# Doorbell.net
KiCad netlist of a schematic drawn in EAGLE
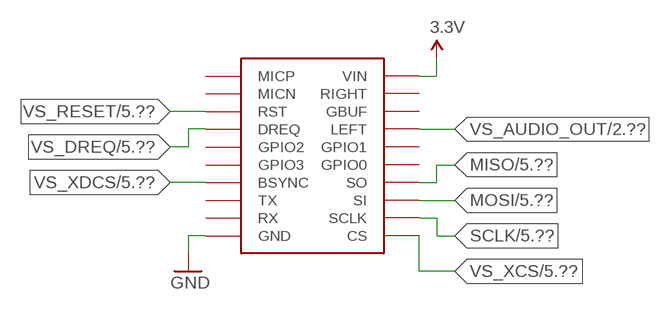
[diagram p0: schematic, sheet 1]
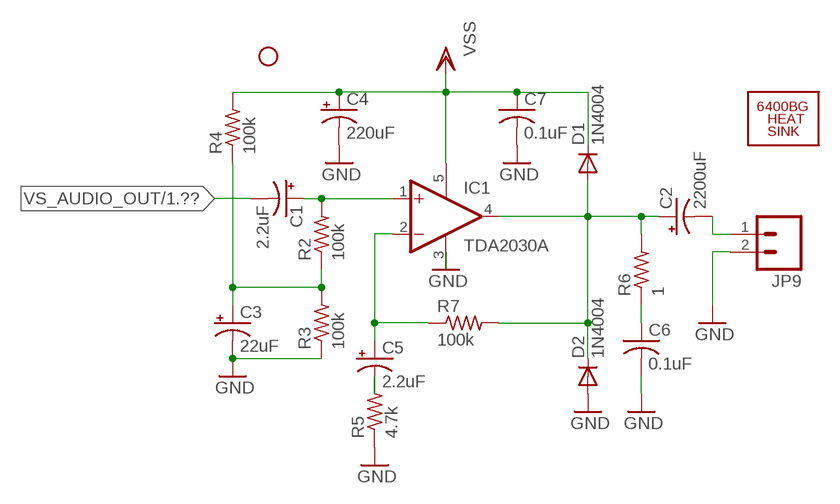
[diagram p1: schematic, sheet 2]
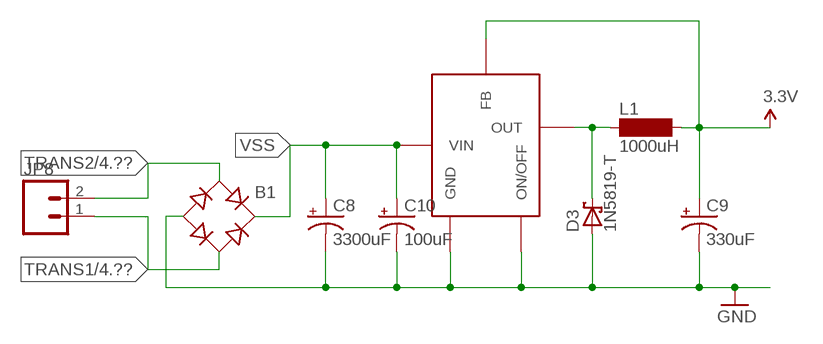
[diagram p2: schematic, sheet 3]
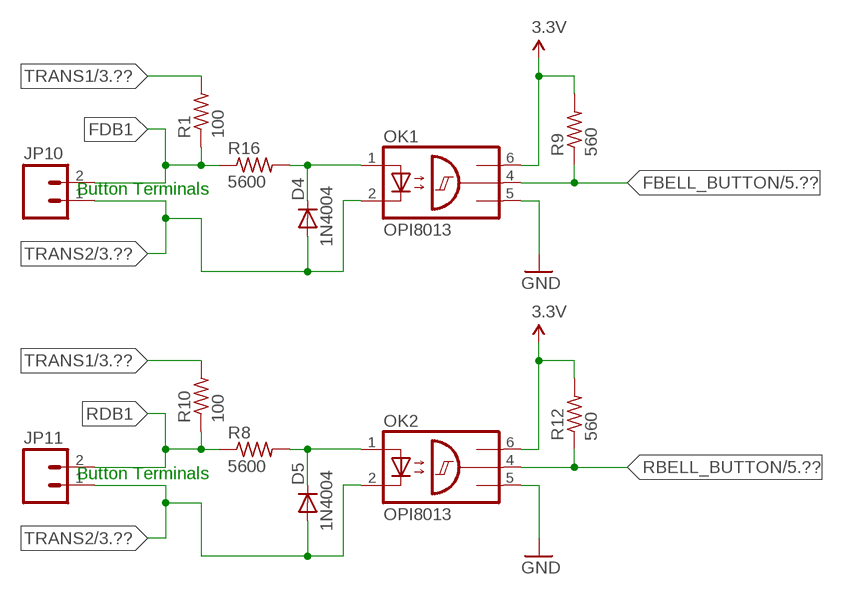
[diagram p3: schematic, sheet 4]
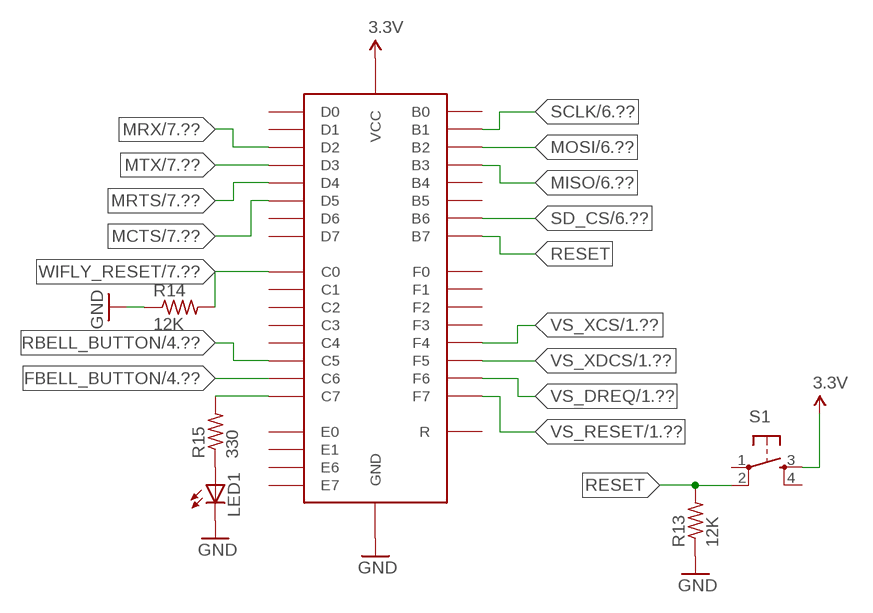
[diagram p4: schematic, sheet 5]
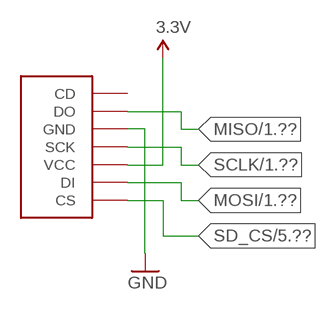
[diagram p5: schematic, sheet 6]
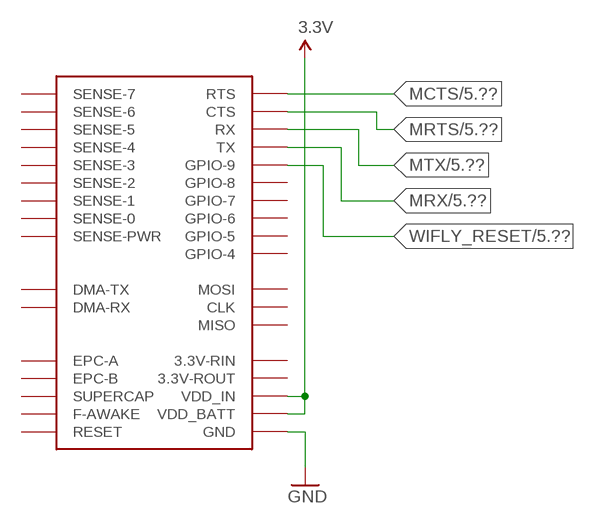
[diagram p6: schematic, sheet 7]

(export (version "E")
  (design (tool "Eeschema 10.0.6"))
  (components
    (comp (ref "U$6")
      (value "WIFLY_BREAKOUT")
      (footprint "eagle-import:SPARKFUN_1X17")
      (libsource (lib "eagle-import") (part "WIFLY_BREAKOUT"))
    )
    (comp (ref "C1")
      (value "2.2uF")
      (footprint "eagle-import:E2-5")
      (libsource (lib "eagle-import") (part "CPOL-USE2-5"))
    )
    (comp (ref "C2")
      (value "2200uF")
      (footprint "eagle-import:E7,5-16")
      (libsource (lib "eagle-import") (part "CPOL-USE7.5-16"))
    )
    (comp (ref "C3")
      (value "22uF")
      (footprint "eagle-import:E2-5")
      (libsource (lib "eagle-import") (part "CPOL-USE2-5"))
    )
    (comp (ref "C4")
      (value "220uF")
      (footprint "eagle-import:E5-10,5")
      (libsource (lib "eagle-import") (part "CPOL-USE5-10.5"))
    )
    (comp (ref "C5")
      (value "2.2uF")
      (footprint "eagle-import:E2-5")
      (libsource (lib "eagle-import") (part "CPOL-USE2-5"))
    )
    (comp (ref "C6")
      (value "0.1uF")
      (footprint "eagle-import:C025-030X050")
      (libsource (lib "eagle-import") (part "C-US025-030X050"))
    )
    (comp (ref "C7")
      (value "0.1uF")
      (footprint "eagle-import:C025-030X050")
      (libsource (lib "eagle-import") (part "C-US025-030X050"))
    )
    (comp (ref "D1")
      (value "1N4004")
      (footprint "eagle-import:DO41-10")
      (libsource (lib "eagle-import") (part "1N4004"))
    )
    (comp (ref "D2")
      (value "1N4004")
      (footprint "eagle-import:DO41-10")
      (libsource (lib "eagle-import") (part "1N4004"))
    )
    (comp (ref "IC1")
      (value "TDA2030A")
      (footprint "eagle-import:CB360")
      (libsource (lib "eagle-import") (part "TDA2030V"))
    )
    (comp (ref "JP7")
      (value "STAND-OFF")
      (footprint "eagle-import:STAND-OFF")
      (libsource (lib "eagle-import") (part "STAND-OFF"))
    )
    (comp (ref "JP9")
      (value "M025MM")
      (footprint "eagle-import:SCREWTERMINAL-5MM-2")
      (libsource (lib "eagle-import") (part "M025MM"))
    )
    (comp (ref "R2")
      (value "100k")
      (footprint "eagle-import:0207_7")
      (libsource (lib "eagle-import") (part "R-US_0207/7"))
    )
    (comp (ref "R3")
      (value "100k")
      (footprint "eagle-import:0207_7")
      (libsource (lib "eagle-import") (part "R-US_0207/7"))
    )
    (comp (ref "R4")
      (value "100k")
      (footprint "eagle-import:0207_7")
      (libsource (lib "eagle-import") (part "R-US_0207/7"))
    )
    (comp (ref "R5")
      (value "4.7k")
      (footprint "eagle-import:0207_7")
      (libsource (lib "eagle-import") (part "R-US_0207/7"))
    )
    (comp (ref "R6")
      (value "1")
      (footprint "eagle-import:0207_7")
      (libsource (lib "eagle-import") (part "R-US_0207/7"))
    )
    (comp (ref "R7")
      (value "100k")
      (footprint "eagle-import:0207_7")
      (libsource (lib "eagle-import") (part "R-US_0207/7"))
    )
    (comp (ref "U$1")
      (value "6400BG_HEATSINK")
      (footprint "eagle-import:6400BG_HEATSINK")
      (libsource (lib "eagle-import") (part "6400BG_HEATSINK"))
    )
    (comp (ref "LED1")
      (value "LED3MM")
      (footprint "eagle-import:LED3MM")
      (libsource (lib "eagle-import") (part "LED3MM"))
    )
    (comp (ref "R13")
      (value "12K")
      (footprint "eagle-import:0207_7")
      (libsource (lib "eagle-import") (part "resistor_R-US_0207/7"))
    )
    (comp (ref "R14")
      (value "12K")
      (footprint "eagle-import:0207_7")
      (libsource (lib "eagle-import") (part "resistor_R-US_0207/7"))
    )
    (comp (ref "R15")
      (value "330")
      (footprint "eagle-import:0207_7")
      (libsource (lib "eagle-import") (part "resistor_R-US_0207/7"))
    )
    (comp (ref "S1")
      (value "TAC_SWITCHPTH")
      (footprint "eagle-import:TACTILE-PTH")
      (libsource (lib "eagle-import") (part "TAC_SWITCHPTH"))
    )
    (comp (ref "U$4")
      (value "AT90USB1286AT90USB1286BREAKOUT")
      (footprint "eagle-import:ADAFRUIT_1X10-BIG")
      (libsource (lib "eagle-import") (part "AT90USB1286AT90USB1286BREAKOUT"))
    )
    (comp (ref "U$3")
      (value "VS1011E")
      (footprint "eagle-import:ADAFRUIT_1X10-BIG")
      (libsource (lib "eagle-import") (part "VS1011E"))
    )
    (comp (ref "B1")
      (value "DBDB101G")
      (footprint "eagle-import:DB")
      (libsource (lib "eagle-import") (part "DB?GDB101"))
    )
    (comp (ref "C8")
      (value "3300uF")
      (footprint "eagle-import:E7,5-18")
      (libsource (lib "eagle-import") (part "CPOL-USE7.5-18"))
    )
    (comp (ref "C9")
      (value "330uF")
      (footprint "eagle-import:E5-8,5")
      (libsource (lib "eagle-import") (part "CPOL-USE5-8.5"))
    )
    (comp (ref "C10")
      (value "100uF")
      (footprint "eagle-import:E5-8,5")
      (libsource (lib "eagle-import") (part "CPOL-USE5-8.5"))
    )
    (comp (ref "D3")
      (value "1N5819-T")
      (footprint "eagle-import:DO41-7.6")
      (libsource (lib "eagle-import") (part "1N5819-T"))
    )
    (comp (ref "JP8")
      (value "M025MM")
      (footprint "eagle-import:SCREWTERMINAL-5MM-2")
      (libsource (lib "eagle-import") (part "M025MM"))
    )
    (comp (ref "L1")
      (value "1000uH")
      (footprint "eagle-import:BS11")
      (libsource (lib "eagle-import") (part "BS11"))
    )
    (comp (ref "U$2")
      (value "LM2575")
      (footprint "eagle-import:LINEAR-TECHNOLOGY_TO220-5")
      (libsource (lib "eagle-import") (part "LM2575"))
    )
    (comp (ref "D4")
      (value "1N4004")
      (footprint "eagle-import:DO41-10")
      (libsource (lib "eagle-import") (part "1N4004"))
    )
    (comp (ref "D5")
      (value "1N4004")
      (footprint "eagle-import:DO41-10")
      (libsource (lib "eagle-import") (part "1N4004"))
    )
    (comp (ref "JP10")
      (value "M025MM")
      (footprint "eagle-import:SCREWTERMINAL-5MM-2")
      (libsource (lib "eagle-import") (part "M025MM"))
    )
    (comp (ref "JP11")
      (value "M025MM")
      (footprint "eagle-import:SCREWTERMINAL-5MM-2")
      (libsource (lib "eagle-import") (part "M025MM"))
    )
    (comp (ref "OK1")
      (value "OPI8013")
      (footprint "eagle-import:DIL06")
      (libsource (lib "eagle-import") (part "OPI8013"))
    )
    (comp (ref "OK2")
      (value "OPI8013")
      (footprint "eagle-import:DIL06")
      (libsource (lib "eagle-import") (part "OPI8013"))
    )
    (comp (ref "R1")
      (value "100")
      (footprint "eagle-import:P0817_22")
      (libsource (lib "eagle-import") (part "R-US_0817/22"))
    )
    (comp (ref "R8")
      (value "5600")
      (footprint "eagle-import:0207_12")
      (libsource (lib "eagle-import") (part "resistor_R-US_0207/12"))
    )
    (comp (ref "R9")
      (value "560")
      (footprint "eagle-import:0207_7")
      (libsource (lib "eagle-import") (part "R-US_0207/7"))
    )
    (comp (ref "R10")
      (value "100")
      (footprint "eagle-import:P0817_22")
      (libsource (lib "eagle-import") (part "R-US_0817/22"))
    )
    (comp (ref "R12")
      (value "560")
      (footprint "eagle-import:0207_7")
      (libsource (lib "eagle-import") (part "R-US_0207/7"))
    )
    (comp (ref "R16")
      (value "5600")
      (footprint "eagle-import:0207_12")
      (libsource (lib "eagle-import") (part "resistor_R-US_0207/12"))
    )
    (comp (ref "U$5")
      (value "MICROSDMICROSDBREAKOUT")
      (footprint "eagle-import:ADAFRUIT_1X08-BIG")
      (libsource (lib "eagle-import") (part "MICROSDMICROSDBREAKOUT"))
    )
  )
  (nets
    (net (code "1") (name "3.3V") (class "Default")
      (node (ref "C9") (pin "+") (pinfunction "+_+") (pintype "passive"))
      (node (ref "L1") (pin "2") (pinfunction "2_2") (pintype "passive"))
      (node (ref "OK1") (pin "6") (pinfunction "VCC_6") (pintype "passive"))
      (node (ref "OK2") (pin "6") (pinfunction "VCC_6") (pintype "passive"))
      (node (ref "R12") (pin "2") (pinfunction "2_2") (pintype "passive"))
      (node (ref "R9") (pin "2") (pinfunction "2_2") (pintype "passive"))
      (node (ref "S1") (pin "3") (pinfunction "3_3") (pintype "passive"))
      (node (ref "U$2") (pin "FB") (pinfunction "FB_FB") (pintype "input"))
      (node (ref "U$3") (pin "VIN") (pinfunction "VIN_VIN") (pintype "bidirectional"))
      (node (ref "U$4") (pin "VCC") (pinfunction "VCC_VCC") (pintype "bidirectional"))
      (node (ref "U$5") (pin "VCC") (pinfunction "VCC_VCC") (pintype "bidirectional"))
      (node (ref "U$6") (pin "VDD_BATT") (pinfunction "VDD_BATT_VDD_BATT") (pintype "bidirectional"))
      (node (ref "U$6") (pin "VDD_IN") (pinfunction "VDD_IN_VDD_IN") (pintype "bidirectional"))
    )
    (net (code "2") (name "FBELL_BUTTON") (class "Default")
      (node (ref "OK1") (pin "4") (pinfunction "OUT_4") (pintype "passive"))
      (node (ref "R9") (pin "1") (pinfunction "1_1") (pintype "passive"))
      (node (ref "U$4") (pin "C6") (pinfunction "C6_C6") (pintype "bidirectional"))
    )
    (net (code "3") (name "FDB1") (class "Default")
      (node (ref "JP10") (pin "2") (pinfunction "2_2") (pintype "passive"))
      (node (ref "R1") (pin "1") (pinfunction "1_1") (pintype "passive"))
      (node (ref "R16") (pin "1") (pinfunction "1_1") (pintype "passive"))
    )
    (net (code "4") (name "GND") (class "Default")
      (node (ref "B1") (pin "-") (pinfunction "-_-") (pintype "passive"))
      (node (ref "C10") (pin "-") (pinfunction "-_-") (pintype "passive"))
      (node (ref "C3") (pin "-") (pinfunction "-_-") (pintype "passive"))
      (node (ref "C4") (pin "-") (pinfunction "-_-") (pintype "passive"))
      (node (ref "C6") (pin "2") (pinfunction "2_2") (pintype "passive"))
      (node (ref "C7") (pin "2") (pinfunction "2_2") (pintype "passive"))
      (node (ref "C8") (pin "-") (pinfunction "-_-") (pintype "passive"))
      (node (ref "C9") (pin "-") (pinfunction "-_-") (pintype "passive"))
      (node (ref "D2") (pin "A") (pinfunction "A_A") (pintype "passive"))
      (node (ref "D3") (pin "A") (pinfunction "A_A") (pintype "passive"))
      (node (ref "IC1") (pin "3") (pinfunction "GND_3") (pintype "power_in"))
      (node (ref "JP9") (pin "2") (pinfunction "2_2") (pintype "passive"))
      (node (ref "LED1") (pin "K") (pinfunction "C_K") (pintype "passive"))
      (node (ref "OK1") (pin "5") (pinfunction "GND_5") (pintype "passive"))
      (node (ref "OK2") (pin "5") (pinfunction "GND_5") (pintype "passive"))
      (node (ref "R13") (pin "1") (pinfunction "1_1") (pintype "passive"))
      (node (ref "R14") (pin "1") (pinfunction "1_1") (pintype "passive"))
      (node (ref "R3") (pin "1") (pinfunction "1_1") (pintype "passive"))
      (node (ref "R5") (pin "1") (pinfunction "1_1") (pintype "passive"))
      (node (ref "U$2") (pin "GND") (pinfunction "GND_GND") (pintype "power_in"))
      (node (ref "U$2") (pin "ON/OFF") (pinfunction "ON/OFF_ON/OFF") (pintype "input"))
      (node (ref "U$3") (pin "GND") (pinfunction "GND_GND") (pintype "bidirectional"))
      (node (ref "U$4") (pin "GND") (pinfunction "GND_GND") (pintype "bidirectional"))
      (node (ref "U$5") (pin "GND") (pinfunction "GND_GND") (pintype "bidirectional"))
      (node (ref "U$6") (pin "GND") (pinfunction "GND_GND") (pintype "bidirectional"))
    )
    (net (code "5") (name "MCTS") (class "Default")
      (node (ref "U$4") (pin "D5") (pinfunction "D5_D5") (pintype "bidirectional"))
      (node (ref "U$6") (pin "RTS") (pinfunction "RTS_RTS") (pintype "bidirectional"))
    )
    (net (code "6") (name "MISO") (class "Default")
      (node (ref "U$3") (pin "SO") (pinfunction "SO_SO") (pintype "bidirectional"))
      (node (ref "U$4") (pin "B3") (pinfunction "B3_B3") (pintype "bidirectional"))
      (node (ref "U$5") (pin "DO") (pinfunction "DO_DO") (pintype "bidirectional"))
    )
    (net (code "7") (name "MOSI") (class "Default")
      (node (ref "U$3") (pin "SI") (pinfunction "SI_SI") (pintype "bidirectional"))
      (node (ref "U$4") (pin "B2") (pinfunction "B2_B2") (pintype "bidirectional"))
      (node (ref "U$5") (pin "DI") (pinfunction "DI_DI") (pintype "bidirectional"))
    )
    (net (code "8") (name "MRTS") (class "Default")
      (node (ref "U$4") (pin "D4") (pinfunction "D4_D4") (pintype "bidirectional"))
      (node (ref "U$6") (pin "CTS") (pinfunction "CTS_CTS") (pintype "bidirectional"))
    )
    (net (code "9") (name "MRX") (class "Default")
      (node (ref "U$4") (pin "D2") (pinfunction "D2_D2") (pintype "bidirectional"))
      (node (ref "U$6") (pin "TX") (pinfunction "TX_TX") (pintype "bidirectional"))
    )
    (net (code "10") (name "MTX") (class "Default")
      (node (ref "U$4") (pin "D3") (pinfunction "D3_D3") (pintype "bidirectional"))
      (node (ref "U$6") (pin "RX") (pinfunction "RX_RX") (pintype "bidirectional"))
    )
    (net (code "11") (name "Net-(C2-Pad-)") (class "Default")
      (node (ref "C2") (pin "-") (pinfunction "-_-") (pintype "passive"))
      (node (ref "JP9") (pin "1") (pinfunction "1_1") (pintype "passive"))
    )
    (net (code "12") (name "Net-(C3-Pad+)") (class "Default")
      (node (ref "C3") (pin "+") (pinfunction "+_+") (pintype "passive"))
      (node (ref "R2") (pin "1") (pinfunction "1_1") (pintype "passive"))
      (node (ref "R3") (pin "2") (pinfunction "2_2") (pintype "passive"))
      (node (ref "R4") (pin "1") (pinfunction "1_1") (pintype "passive"))
    )
    (net (code "13") (name "Net-(C5-Pad-)") (class "Default")
      (node (ref "C5") (pin "-") (pinfunction "-_-") (pintype "passive"))
      (node (ref "R5") (pin "2") (pinfunction "2_2") (pintype "passive"))
    )
    (net (code "14") (name "Net-(C6-Pad1)") (class "Default")
      (node (ref "C6") (pin "1") (pinfunction "1_1") (pintype "passive"))
      (node (ref "R6") (pin "1") (pinfunction "1_1") (pintype "passive"))
    )
    (net (code "15") (name "Net-(D3-PadC)") (class "Default")
      (node (ref "D3") (pin "C") (pinfunction "C_C") (pintype "passive"))
      (node (ref "L1") (pin "1") (pinfunction "1_1") (pintype "passive"))
      (node (ref "U$2") (pin "OUT") (pinfunction "OUT_OUT") (pintype "power_in"))
    )
    (net (code "16") (name "Net-(IC1-+IN)") (class "Default")
      (node (ref "C1") (pin "+") (pinfunction "+_+") (pintype "passive"))
      (node (ref "IC1") (pin "1") (pinfunction "+IN_1") (pintype "input"))
      (node (ref "R2") (pin "2") (pinfunction "2_2") (pintype "passive"))
    )
    (net (code "17") (name "Net-(IC1--IN)") (class "Default")
      (node (ref "C5") (pin "+") (pinfunction "+_+") (pintype "passive"))
      (node (ref "IC1") (pin "2") (pinfunction "-IN_2") (pintype "input"))
      (node (ref "R7") (pin "1") (pinfunction "1_1") (pintype "passive"))
    )
    (net (code "18") (name "Net-(IC1-OUT)") (class "Default")
      (node (ref "C2") (pin "+") (pinfunction "+_+") (pintype "passive"))
      (node (ref "D1") (pin "A") (pinfunction "A_A") (pintype "passive"))
      (node (ref "D2") (pin "C") (pinfunction "C_C") (pintype "passive"))
      (node (ref "IC1") (pin "4") (pinfunction "OUT_4") (pintype "output"))
      (node (ref "R6") (pin "2") (pinfunction "2_2") (pintype "passive"))
      (node (ref "R7") (pin "2") (pinfunction "2_2") (pintype "passive"))
    )
    (net (code "19") (name "Net-(LED1-PadA)") (class "Default")
      (node (ref "LED1") (pin "A") (pinfunction "A_A") (pintype "passive"))
      (node (ref "R15") (pin "1") (pinfunction "1_1") (pintype "passive"))
    )
    (net (code "20") (name "Net-(OK1-A)") (class "Default")
      (node (ref "D4") (pin "C") (pinfunction "C_C") (pintype "passive"))
      (node (ref "OK1") (pin "1") (pinfunction "A_1") (pintype "passive"))
      (node (ref "R16") (pin "2") (pinfunction "2_2") (pintype "passive"))
    )
    (net (code "21") (name "Net-(OK2-A)") (class "Default")
      (node (ref "D5") (pin "C") (pinfunction "C_C") (pintype "passive"))
      (node (ref "OK2") (pin "1") (pinfunction "A_1") (pintype "passive"))
      (node (ref "R8") (pin "2") (pinfunction "2_2") (pintype "passive"))
    )
    (net (code "22") (name "Net-(R15-Pad2)") (class "Default")
      (node (ref "R15") (pin "2") (pinfunction "2_2") (pintype "passive"))
      (node (ref "U$4") (pin "C7") (pinfunction "C7_C7") (pintype "bidirectional"))
    )
    (net (code "23") (name "RBELL_BUTTON") (class "Default")
      (node (ref "OK2") (pin "4") (pinfunction "OUT_4") (pintype "passive"))
      (node (ref "R12") (pin "1") (pinfunction "1_1") (pintype "passive"))
      (node (ref "U$4") (pin "C5") (pinfunction "C5_C5") (pintype "bidirectional"))
    )
    (net (code "24") (name "RDB1") (class "Default")
      (node (ref "JP11") (pin "2") (pinfunction "2_2") (pintype "passive"))
      (node (ref "R10") (pin "1") (pinfunction "1_1") (pintype "passive"))
      (node (ref "R8") (pin "1") (pinfunction "1_1") (pintype "passive"))
    )
    (net (code "25") (name "RESET") (class "Default")
      (node (ref "R13") (pin "2") (pinfunction "2_2") (pintype "passive"))
      (node (ref "S1") (pin "2") (pinfunction "2_2") (pintype "passive"))
      (node (ref "U$4") (pin "B7") (pinfunction "B7_B7") (pintype "bidirectional"))
    )
    (net (code "26") (name "SCLK") (class "Default")
      (node (ref "U$3") (pin "SCLK") (pinfunction "SCLK_SCLK") (pintype "bidirectional"))
      (node (ref "U$4") (pin "B1") (pinfunction "B1_B1") (pintype "bidirectional"))
      (node (ref "U$5") (pin "SCK") (pinfunction "SCK_SCK") (pintype "bidirectional"))
    )
    (net (code "27") (name "SD_CS") (class "Default")
      (node (ref "U$4") (pin "B6") (pinfunction "B6_B6") (pintype "bidirectional"))
      (node (ref "U$5") (pin "CS") (pinfunction "CS_CS") (pintype "bidirectional"))
    )
    (net (code "28") (name "TRANS1") (class "Default")
      (node (ref "B1") (pin "AC2") (pinfunction "AC2_AC2") (pintype "passive"))
      (node (ref "JP8") (pin "1") (pinfunction "1_1") (pintype "passive"))
      (node (ref "R1") (pin "2") (pinfunction "2_2") (pintype "passive"))
      (node (ref "R10") (pin "2") (pinfunction "2_2") (pintype "passive"))
    )
    (net (code "29") (name "TRANS2") (class "Default")
      (node (ref "B1") (pin "AC1") (pinfunction "AC1_AC1") (pintype "passive"))
      (node (ref "D4") (pin "A") (pinfunction "A_A") (pintype "passive"))
      (node (ref "D5") (pin "A") (pinfunction "A_A") (pintype "passive"))
      (node (ref "JP10") (pin "1") (pinfunction "1_1") (pintype "passive"))
      (node (ref "JP11") (pin "1") (pinfunction "1_1") (pintype "passive"))
      (node (ref "JP8") (pin "2") (pinfunction "2_2") (pintype "passive"))
      (node (ref "OK1") (pin "2") (pinfunction "C_2") (pintype "passive"))
      (node (ref "OK2") (pin "2") (pinfunction "C_2") (pintype "passive"))
    )
    (net (code "30") (name "VSS") (class "Default")
      (node (ref "B1") (pin "+") (pinfunction "+_+") (pintype "passive"))
      (node (ref "C10") (pin "+") (pinfunction "+_+") (pintype "passive"))
      (node (ref "C4") (pin "+") (pinfunction "+_+") (pintype "passive"))
      (node (ref "C7") (pin "1") (pinfunction "1_1") (pintype "passive"))
      (node (ref "C8") (pin "+") (pinfunction "+_+") (pintype "passive"))
      (node (ref "D1") (pin "C") (pinfunction "C_C") (pintype "passive"))
      (node (ref "IC1") (pin "5") (pinfunction "V+_5") (pintype "power_in"))
      (node (ref "R4") (pin "2") (pinfunction "2_2") (pintype "passive"))
      (node (ref "U$2") (pin "VIN") (pinfunction "VIN_VIN") (pintype "power_in"))
    )
    (net (code "31") (name "VS_AUDIO_OUT") (class "Default")
      (node (ref "C1") (pin "-") (pinfunction "-_-") (pintype "passive"))
      (node (ref "U$3") (pin "LEFT") (pinfunction "LEFT_LEFT") (pintype "bidirectional"))
    )
    (net (code "32") (name "VS_DREQ") (class "Default")
      (node (ref "U$3") (pin "DREQ") (pinfunction "DREQ_DREQ") (pintype "bidirectional"))
      (node (ref "U$4") (pin "F6") (pinfunction "F6_F6") (pintype "bidirectional"))
    )
    (net (code "33") (name "VS_RESET") (class "Default")
      (node (ref "U$3") (pin "RST") (pinfunction "RST_RST") (pintype "bidirectional"))
      (node (ref "U$4") (pin "F7") (pinfunction "F7_F7") (pintype "bidirectional"))
    )
    (net (code "34") (name "VS_XCS") (class "Default")
      (node (ref "U$3") (pin "CS") (pinfunction "CS_CS") (pintype "bidirectional"))
      (node (ref "U$4") (pin "F4") (pinfunction "F4_F4") (pintype "bidirectional"))
    )
    (net (code "35") (name "VS_XDCS") (class "Default")
      (node (ref "U$3") (pin "BSYNC") (pinfunction "BSYNC_BSYNC") (pintype "bidirectional"))
      (node (ref "U$4") (pin "F5") (pinfunction "F5_F5") (pintype "bidirectional"))
    )
    (net (code "36") (name "WIFLY_RESET") (class "Default")
      (node (ref "R14") (pin "2") (pinfunction "2_2") (pintype "passive"))
      (node (ref "U$4") (pin "C0") (pinfunction "C0_C0") (pintype "bidirectional"))
      (node (ref "U$6") (pin "GPIO-9") (pinfunction "GPIO-9_GPIO-9") (pintype "bidirectional"))
    )
    (net (code "37") (name "unconnected-(S1-Pad1)") (class "Default")
      (node (ref "S1") (pin "1") (pinfunction "1_1") (pintype "passive"))
    )
    (net (code "38") (name "unconnected-(S1-Pad4)") (class "Default")
      (node (ref "S1") (pin "4") (pinfunction "4_4") (pintype "passive"))
    )
    (net (code "39") (name "unconnected-(U$3-PadGBUF)") (class "Default")
      (node (ref "U$3") (pin "GBUF") (pinfunction "GBUF_GBUF") (pintype "bidirectional"))
    )
    (net (code "40") (name "unconnected-(U$3-PadGPIO0)") (class "Default")
      (node (ref "U$3") (pin "GPIO0") (pinfunction "GPIO0_GPIO0") (pintype "bidirectional"))
    )
    (net (code "41") (name "unconnected-(U$3-PadGPIO1)") (class "Default")
      (node (ref "U$3") (pin "GPIO1") (pinfunction "GPIO1_GPIO1") (pintype "bidirectional"))
    )
    (net (code "42") (name "unconnected-(U$3-PadGPIO2)") (class "Default")
      (node (ref "U$3") (pin "GPIO2") (pinfunction "GPIO2_GPIO2") (pintype "bidirectional"))
    )
    (net (code "43") (name "unconnected-(U$3-PadGPIO3)") (class "Default")
      (node (ref "U$3") (pin "GPIO3") (pinfunction "GPIO3_GPIO3") (pintype "bidirectional"))
    )
    (net (code "44") (name "unconnected-(U$3-PadMICN)") (class "Default")
      (node (ref "U$3") (pin "MICN") (pinfunction "MICN_MICN") (pintype "bidirectional"))
    )
    (net (code "45") (name "unconnected-(U$3-PadMICP)") (class "Default")
      (node (ref "U$3") (pin "MICP") (pinfunction "MICP_MICP") (pintype "bidirectional"))
    )
    (net (code "46") (name "unconnected-(U$3-PadRIGHT)") (class "Default")
      (node (ref "U$3") (pin "RIGHT") (pinfunction "RIGHT_RIGHT") (pintype "bidirectional"))
    )
    (net (code "47") (name "unconnected-(U$3-PadRX)") (class "Default")
      (node (ref "U$3") (pin "RX") (pinfunction "RX_RX") (pintype "bidirectional"))
    )
    (net (code "48") (name "unconnected-(U$3-PadTX)") (class "Default")
      (node (ref "U$3") (pin "TX") (pinfunction "TX_TX") (pintype "bidirectional"))
    )
    (net (code "49") (name "unconnected-(U$4-PadB0)") (class "Default")
      (node (ref "U$4") (pin "B0") (pinfunction "B0_B0") (pintype "bidirectional"))
    )
    (net (code "50") (name "unconnected-(U$4-PadB4)") (class "Default")
      (node (ref "U$4") (pin "B4") (pinfunction "B4_B4") (pintype "bidirectional"))
    )
    (net (code "51") (name "unconnected-(U$4-PadB5)") (class "Default")
      (node (ref "U$4") (pin "B5") (pinfunction "B5_B5") (pintype "bidirectional"))
    )
    (net (code "52") (name "unconnected-(U$4-PadC1)") (class "Default")
      (node (ref "U$4") (pin "C1") (pinfunction "C1_C1") (pintype "bidirectional"))
    )
    (net (code "53") (name "unconnected-(U$4-PadC2)") (class "Default")
      (node (ref "U$4") (pin "C2") (pinfunction "C2_C2") (pintype "bidirectional"))
    )
    (net (code "54") (name "unconnected-(U$4-PadC3)") (class "Default")
      (node (ref "U$4") (pin "C3") (pinfunction "C3_C3") (pintype "bidirectional"))
    )
    (net (code "55") (name "unconnected-(U$4-PadC4)") (class "Default")
      (node (ref "U$4") (pin "C4") (pinfunction "C4_C4") (pintype "bidirectional"))
    )
    (net (code "56") (name "unconnected-(U$4-PadD0)") (class "Default")
      (node (ref "U$4") (pin "D0") (pinfunction "D0_D0") (pintype "bidirectional"))
    )
    (net (code "57") (name "unconnected-(U$4-PadD1)") (class "Default")
      (node (ref "U$4") (pin "D1") (pinfunction "D1_D1") (pintype "bidirectional"))
    )
    (net (code "58") (name "unconnected-(U$4-PadD6)") (class "Default")
      (node (ref "U$4") (pin "D6") (pinfunction "D6_D6") (pintype "bidirectional"))
    )
    (net (code "59") (name "unconnected-(U$4-PadD7)") (class "Default")
      (node (ref "U$4") (pin "D7") (pinfunction "D7_D7") (pintype "bidirectional"))
    )
    (net (code "60") (name "unconnected-(U$4-PadE0)") (class "Default")
      (node (ref "U$4") (pin "E0") (pinfunction "E0_E0") (pintype "bidirectional"))
    )
    (net (code "61") (name "unconnected-(U$4-PadE1)") (class "Default")
      (node (ref "U$4") (pin "E1") (pinfunction "E1_E1") (pintype "bidirectional"))
    )
    (net (code "62") (name "unconnected-(U$4-PadE6)") (class "Default")
      (node (ref "U$4") (pin "E6") (pinfunction "E6_E6") (pintype "bidirectional"))
    )
    (net (code "63") (name "unconnected-(U$4-PadE7)") (class "Default")
      (node (ref "U$4") (pin "E7") (pinfunction "E7_E7") (pintype "bidirectional"))
    )
    (net (code "64") (name "unconnected-(U$4-PadF0)") (class "Default")
      (node (ref "U$4") (pin "F0") (pinfunction "F0_F0") (pintype "bidirectional"))
    )
    (net (code "65") (name "unconnected-(U$4-PadF1)") (class "Default")
      (node (ref "U$4") (pin "F1") (pinfunction "F1_F1") (pintype "bidirectional"))
    )
    (net (code "66") (name "unconnected-(U$4-PadF2)") (class "Default")
      (node (ref "U$4") (pin "F2") (pinfunction "F2_F2") (pintype "bidirectional"))
    )
    (net (code "67") (name "unconnected-(U$4-PadF3)") (class "Default")
      (node (ref "U$4") (pin "F3") (pinfunction "F3_F3") (pintype "bidirectional"))
    )
    (net (code "68") (name "unconnected-(U$4-PadR)") (class "Default")
      (node (ref "U$4") (pin "R") (pinfunction "R_R") (pintype "bidirectional"))
    )
    (net (code "69") (name "unconnected-(U$5-PadCD)") (class "Default")
      (node (ref "U$5") (pin "CD") (pinfunction "CD_CD") (pintype "bidirectional"))
    )
    (net (code "70") (name "unconnected-(U$6-F-AWAKE-PadF_AWAKE)") (class "Default")
      (node (ref "U$6") (pin "F_AWAKE") (pinfunction "F-AWAKE_F_AWAKE") (pintype "bidirectional"))
    )
    (net (code "71") (name "unconnected-(U$6-Pad3.3V-RIN)") (class "Default")
      (node (ref "U$6") (pin "3.3V-RIN") (pinfunction "3.3V-RIN_3.3V-RIN") (pintype "bidirectional"))
    )
    (net (code "72") (name "unconnected-(U$6-Pad3.3V-ROUT)") (class "Default")
      (node (ref "U$6") (pin "3.3V-ROUT") (pinfunction "3.3V-ROUT_3.3V-ROUT") (pintype "bidirectional"))
    )
    (net (code "73") (name "unconnected-(U$6-PadCLK)") (class "Default")
      (node (ref "U$6") (pin "CLK") (pinfunction "CLK_CLK") (pintype "bidirectional"))
    )
    (net (code "74") (name "unconnected-(U$6-PadDMA-RX)") (class "Default")
      (node (ref "U$6") (pin "DMA-RX") (pinfunction "DMA-RX_DMA-RX") (pintype "bidirectional"))
    )
    (net (code "75") (name "unconnected-(U$6-PadDMA-TX)") (class "Default")
      (node (ref "U$6") (pin "DMA-TX") (pinfunction "DMA-TX_DMA-TX") (pintype "bidirectional"))
    )
    (net (code "76") (name "unconnected-(U$6-PadEPC-A)") (class "Default")
      (node (ref "U$6") (pin "EPC-A") (pinfunction "EPC-A_EPC-A") (pintype "bidirectional"))
    )
    (net (code "77") (name "unconnected-(U$6-PadEPC-B)") (class "Default")
      (node (ref "U$6") (pin "EPC-B") (pinfunction "EPC-B_EPC-B") (pintype "bidirectional"))
    )
    (net (code "78") (name "unconnected-(U$6-PadGPIO-4)") (class "Default")
      (node (ref "U$6") (pin "GPIO-4") (pinfunction "GPIO-4_GPIO-4") (pintype "bidirectional"))
    )
    (net (code "79") (name "unconnected-(U$6-PadGPIO-5)") (class "Default")
      (node (ref "U$6") (pin "GPIO-5") (pinfunction "GPIO-5_GPIO-5") (pintype "bidirectional"))
    )
    (net (code "80") (name "unconnected-(U$6-PadGPIO-6)") (class "Default")
      (node (ref "U$6") (pin "GPIO-6") (pinfunction "GPIO-6_GPIO-6") (pintype "bidirectional"))
    )
    (net (code "81") (name "unconnected-(U$6-PadGPIO-7)") (class "Default")
      (node (ref "U$6") (pin "GPIO-7") (pinfunction "GPIO-7_GPIO-7") (pintype "bidirectional"))
    )
    (net (code "82") (name "unconnected-(U$6-PadGPIO-8)") (class "Default")
      (node (ref "U$6") (pin "GPIO-8") (pinfunction "GPIO-8_GPIO-8") (pintype "bidirectional"))
    )
    (net (code "83") (name "unconnected-(U$6-PadMISO)") (class "Default")
      (node (ref "U$6") (pin "MISO") (pinfunction "MISO_MISO") (pintype "bidirectional"))
    )
    (net (code "84") (name "unconnected-(U$6-PadMOSI)") (class "Default")
      (node (ref "U$6") (pin "MOSI") (pinfunction "MOSI_MOSI") (pintype "bidirectional"))
    )
    (net (code "85") (name "unconnected-(U$6-PadRESET)") (class "Default")
      (node (ref "U$6") (pin "RESET") (pinfunction "RESET_RESET") (pintype "bidirectional"))
    )
    (net (code "86") (name "unconnected-(U$6-PadSENSE-0)") (class "Default")
      (node (ref "U$6") (pin "SENSE-0") (pinfunction "SENSE-0_SENSE-0") (pintype "bidirectional"))
    )
    (net (code "87") (name "unconnected-(U$6-PadSENSE-1)") (class "Default")
      (node (ref "U$6") (pin "SENSE-1") (pinfunction "SENSE-1_SENSE-1") (pintype "bidirectional"))
    )
    (net (code "88") (name "unconnected-(U$6-PadSENSE-2)") (class "Default")
      (node (ref "U$6") (pin "SENSE-2") (pinfunction "SENSE-2_SENSE-2") (pintype "bidirectional"))
    )
    (net (code "89") (name "unconnected-(U$6-PadSENSE-3)") (class "Default")
      (node (ref "U$6") (pin "SENSE-3") (pinfunction "SENSE-3_SENSE-3") (pintype "bidirectional"))
    )
    (net (code "90") (name "unconnected-(U$6-PadSENSE-4)") (class "Default")
      (node (ref "U$6") (pin "SENSE-4") (pinfunction "SENSE-4_SENSE-4") (pintype "bidirectional"))
    )
    (net (code "91") (name "unconnected-(U$6-PadSENSE-5)") (class "Default")
      (node (ref "U$6") (pin "SENSE-5") (pinfunction "SENSE-5_SENSE-5") (pintype "bidirectional"))
    )
    (net (code "92") (name "unconnected-(U$6-PadSENSE-6)") (class "Default")
      (node (ref "U$6") (pin "SENSE-6") (pinfunction "SENSE-6_SENSE-6") (pintype "bidirectional"))
    )
    (net (code "93") (name "unconnected-(U$6-PadSENSE-7)") (class "Default")
      (node (ref "U$6") (pin "SENSE-7") (pinfunction "SENSE-7_SENSE-7") (pintype "bidirectional"))
    )
    (net (code "94") (name "unconnected-(U$6-PadSENSE-PWR)") (class "Default")
      (node (ref "U$6") (pin "SENSE-PWR") (pinfunction "SENSE-PWR_SENSE-PWR") (pintype "bidirectional"))
    )
    (net (code "95") (name "unconnected-(U$6-PadSUPERCAP)") (class "Default")
      (node (ref "U$6") (pin "SUPERCAP") (pinfunction "SUPERCAP_SUPERCAP") (pintype "bidirectional"))
    )
  )
)
